# dev-board.net
KiCad netlist of a schematic drawn in EAGLE
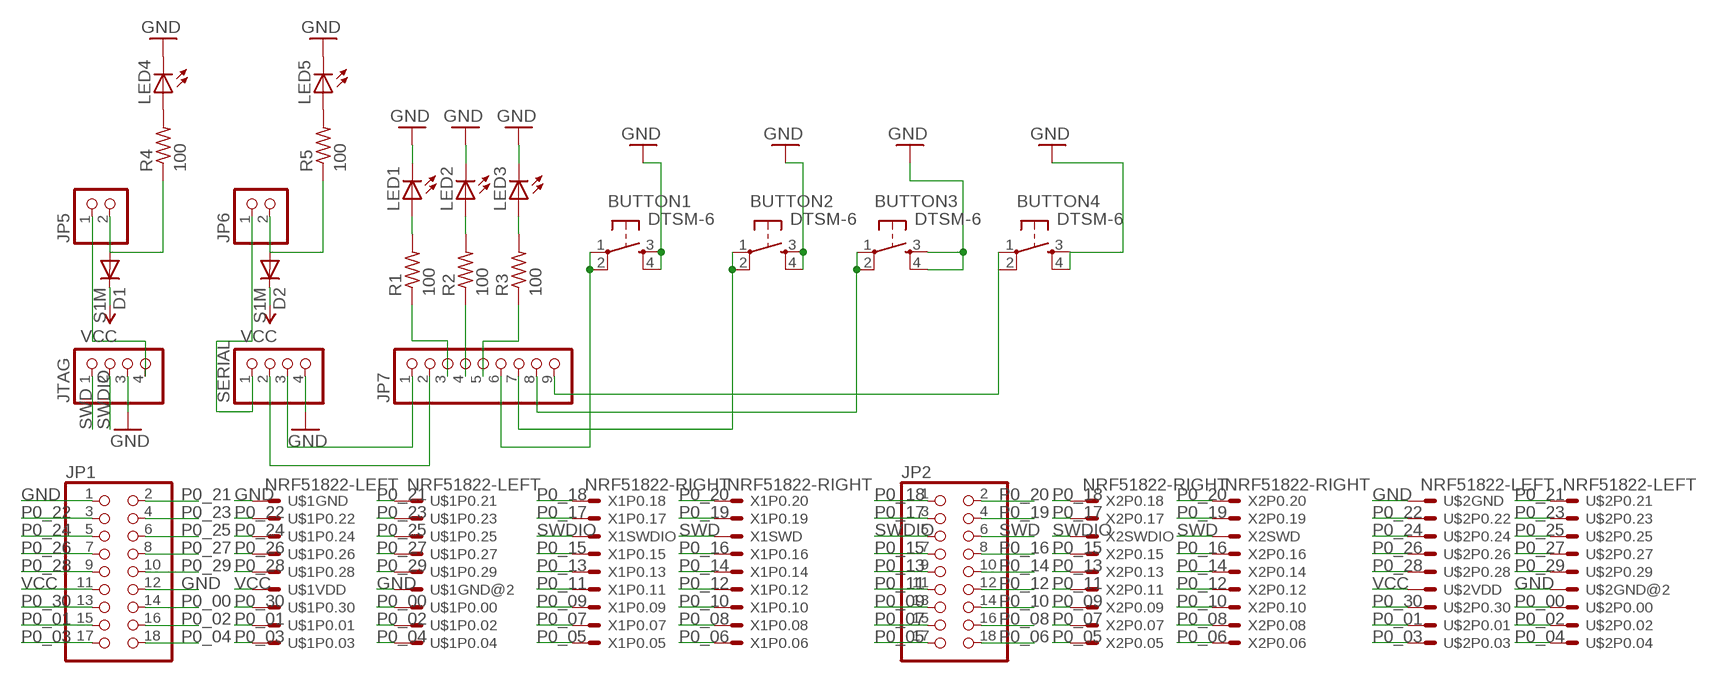
[diagram p0: schematic, sheet 1]

(export (version "E")
  (design (tool "Eeschema 10.0.6"))
  (components
    (comp (ref "BUTTON1")
      (value "DTSM-6")
      (footprint "eagle-import:DTSM-6")
      (libsource (lib "eagle-import") (part "DTSM-6"))
    )
    (comp (ref "BUTTON2")
      (value "DTSM-6")
      (footprint "eagle-import:DTSM-6")
      (libsource (lib "eagle-import") (part "DTSM-6"))
    )
    (comp (ref "BUTTON3")
      (value "DTSM-6")
      (footprint "eagle-import:DTSM-6")
      (libsource (lib "eagle-import") (part "DTSM-6"))
    )
    (comp (ref "BUTTON4")
      (value "DTSM-6")
      (footprint "eagle-import:DTSM-6")
      (libsource (lib "eagle-import") (part "DTSM-6"))
    )
    (comp (ref "D1")
      (value "S1M")
      (footprint "eagle-import:SMA")
      (libsource (lib "eagle-import") (part "S1M"))
    )
    (comp (ref "D2")
      (value "S1M")
      (footprint "eagle-import:SMA")
      (libsource (lib "eagle-import") (part "S1M"))
    )
    (comp (ref "JP1")
      (value "PINHD-2X9")
      (footprint "eagle-import:2X09")
      (libsource (lib "eagle-import") (part "PINHD-2X9"))
    )
    (comp (ref "JP2")
      (value "PINHD-2X9")
      (footprint "eagle-import:2X09")
      (libsource (lib "eagle-import") (part "PINHD-2X9"))
    )
    (comp (ref "JP5")
      (value "PINHD-1X2")
      (footprint "eagle-import:1X02")
      (libsource (lib "eagle-import") (part "PINHD-1X2"))
    )
    (comp (ref "JP6")
      (value "PINHD-1X2")
      (footprint "eagle-import:1X02")
      (libsource (lib "eagle-import") (part "PINHD-1X2"))
    )
    (comp (ref "JP7")
      (value "PINHD-1X9")
      (footprint "eagle-import:1X09")
      (libsource (lib "eagle-import") (part "PINHD-1X9"))
    )
    (comp (ref "JTAG")
      (value "PINHD-1X4")
      (footprint "eagle-import:1X04")
      (libsource (lib "eagle-import") (part "PINHD-1X4"))
    )
    (comp (ref "LED1")
      (value "LEDSML0603")
      (footprint "eagle-import:SML0603")
      (libsource (lib "eagle-import") (part "LEDSML0603"))
    )
    (comp (ref "LED2")
      (value "LEDSML0603")
      (footprint "eagle-import:SML0603")
      (libsource (lib "eagle-import") (part "LEDSML0603"))
    )
    (comp (ref "LED3")
      (value "LEDSML0603")
      (footprint "eagle-import:SML0603")
      (libsource (lib "eagle-import") (part "LEDSML0603"))
    )
    (comp (ref "LED4")
      (value "LEDSML0603")
      (footprint "eagle-import:SML0603")
      (libsource (lib "eagle-import") (part "LEDSML0603"))
    )
    (comp (ref "LED5")
      (value "LEDSML0603")
      (footprint "eagle-import:SML0603")
      (libsource (lib "eagle-import") (part "LEDSML0603"))
    )
    (comp (ref "R1")
      (value "100")
      (footprint "eagle-import:R0603")
      (libsource (lib "eagle-import") (part "R-US_R0603"))
    )
    (comp (ref "R2")
      (value "100")
      (footprint "eagle-import:R0603")
      (libsource (lib "eagle-import") (part "R-US_R0603"))
    )
    (comp (ref "R3")
      (value "100")
      (footprint "eagle-import:R0603")
      (libsource (lib "eagle-import") (part "R-US_R0603"))
    )
    (comp (ref "R4")
      (value "100")
      (footprint "eagle-import:R0603")
      (libsource (lib "eagle-import") (part "R-US_R0603"))
    )
    (comp (ref "R5")
      (value "100")
      (footprint "eagle-import:R0603")
      (libsource (lib "eagle-import") (part "R-US_R0603"))
    )
    (comp (ref "SERIAL")
      (value "PINHD-1X4")
      (footprint "eagle-import:1X04")
      (libsource (lib "eagle-import") (part "PINHD-1X4"))
    )
    (comp (ref "U$1")
      (value "NRF51822-LEFT")
      (footprint "eagle-import:NRF51822-LEFT")
      (fields (field (name "MPN") "NRF51822-left"))
      (libsource (lib "eagle-import") (part "NRF51822-LEFT"))
    )
    (comp (ref "U$2")
      (value "NRF51822-LEFT")
      (footprint "eagle-import:NRF51822-LEFT")
      (fields (field (name "MPN") "NRF51822-left"))
      (libsource (lib "eagle-import") (part "NRF51822-LEFT"))
    )
    (comp (ref "X1")
      (value "NRF51822-RIGHT")
      (footprint "eagle-import:NRF51822-RIGHT")
      (fields (field (name "MPN") "NRF51822-right"))
      (libsource (lib "eagle-import") (part "NRF51822-RIGHT"))
    )
    (comp (ref "X2")
      (value "NRF51822-RIGHT")
      (footprint "eagle-import:NRF51822-RIGHT")
      (fields (field (name "MPN") "NRF51822-right"))
      (libsource (lib "eagle-import") (part "NRF51822-RIGHT"))
    )
  )
  (nets
    (net (code "1") (name "/P0_00") (class "Default")
      (node (ref "JP1") (pin "14") (pinfunction "14_14") (pintype "passive"))
      (node (ref "U$1") (pin "14") (pinfunction "S_14") (pintype "passive"))
      (node (ref "U$2") (pin "14") (pinfunction "S_14") (pintype "passive"))
    )
    (net (code "2") (name "/P0_01") (class "Default")
      (node (ref "JP1") (pin "15") (pinfunction "15_15") (pintype "passive"))
      (node (ref "U$1") (pin "15") (pinfunction "S_15") (pintype "passive"))
      (node (ref "U$2") (pin "15") (pinfunction "S_15") (pintype "passive"))
    )
    (net (code "3") (name "/P0_02") (class "Default")
      (node (ref "JP1") (pin "16") (pinfunction "16_16") (pintype "passive"))
      (node (ref "U$1") (pin "16") (pinfunction "S_16") (pintype "passive"))
      (node (ref "U$2") (pin "16") (pinfunction "S_16") (pintype "passive"))
    )
    (net (code "4") (name "/P0_03") (class "Default")
      (node (ref "JP1") (pin "17") (pinfunction "17_17") (pintype "passive"))
      (node (ref "U$1") (pin "17") (pinfunction "S_17") (pintype "passive"))
      (node (ref "U$2") (pin "17") (pinfunction "S_17") (pintype "passive"))
    )
    (net (code "5") (name "/P0_04") (class "Default")
      (node (ref "JP1") (pin "18") (pinfunction "18_18") (pintype "passive"))
      (node (ref "U$1") (pin "18") (pinfunction "S_18") (pintype "passive"))
      (node (ref "U$2") (pin "18") (pinfunction "S_18") (pintype "passive"))
    )
    (net (code "6") (name "/P0_05") (class "Default")
      (node (ref "JP2") (pin "17") (pinfunction "17_17") (pintype "passive"))
      (node (ref "X1") (pin "17") (pinfunction "S_17") (pintype "passive"))
      (node (ref "X2") (pin "17") (pinfunction "S_17") (pintype "passive"))
    )
    (net (code "7") (name "/P0_06") (class "Default")
      (node (ref "JP2") (pin "18") (pinfunction "18_18") (pintype "passive"))
      (node (ref "X1") (pin "18") (pinfunction "S_18") (pintype "passive"))
      (node (ref "X2") (pin "18") (pinfunction "S_18") (pintype "passive"))
    )
    (net (code "8") (name "/P0_07") (class "Default")
      (node (ref "JP2") (pin "15") (pinfunction "15_15") (pintype "passive"))
      (node (ref "X1") (pin "15") (pinfunction "S_15") (pintype "passive"))
      (node (ref "X2") (pin "15") (pinfunction "S_15") (pintype "passive"))
    )
    (net (code "9") (name "/P0_08") (class "Default")
      (node (ref "JP2") (pin "16") (pinfunction "16_16") (pintype "passive"))
      (node (ref "X1") (pin "16") (pinfunction "S_16") (pintype "passive"))
      (node (ref "X2") (pin "16") (pinfunction "S_16") (pintype "passive"))
    )
    (net (code "10") (name "/P0_09") (class "Default")
      (node (ref "JP2") (pin "13") (pinfunction "13_13") (pintype "passive"))
      (node (ref "X1") (pin "13") (pinfunction "S_13") (pintype "passive"))
      (node (ref "X2") (pin "13") (pinfunction "S_13") (pintype "passive"))
    )
    (net (code "11") (name "/P0_10") (class "Default")
      (node (ref "JP2") (pin "14") (pinfunction "14_14") (pintype "passive"))
      (node (ref "X1") (pin "14") (pinfunction "S_14") (pintype "passive"))
      (node (ref "X2") (pin "14") (pinfunction "S_14") (pintype "passive"))
    )
    (net (code "12") (name "/P0_11") (class "Default")
      (node (ref "JP2") (pin "11") (pinfunction "11_11") (pintype "passive"))
      (node (ref "X1") (pin "11") (pinfunction "S_11") (pintype "passive"))
      (node (ref "X2") (pin "11") (pinfunction "S_11") (pintype "passive"))
    )
    (net (code "13") (name "/P0_12") (class "Default")
      (node (ref "JP2") (pin "12") (pinfunction "12_12") (pintype "passive"))
      (node (ref "X1") (pin "12") (pinfunction "S_12") (pintype "passive"))
      (node (ref "X2") (pin "12") (pinfunction "S_12") (pintype "passive"))
    )
    (net (code "14") (name "/P0_13") (class "Default")
      (node (ref "JP2") (pin "9") (pinfunction "9_9") (pintype "passive"))
      (node (ref "X1") (pin "9") (pinfunction "S_9") (pintype "passive"))
      (node (ref "X2") (pin "9") (pinfunction "S_9") (pintype "passive"))
    )
    (net (code "15") (name "/P0_14") (class "Default")
      (node (ref "JP2") (pin "10") (pinfunction "10_10") (pintype "passive"))
      (node (ref "X1") (pin "10") (pinfunction "S_10") (pintype "passive"))
      (node (ref "X2") (pin "10") (pinfunction "S_10") (pintype "passive"))
    )
    (net (code "16") (name "/P0_15") (class "Default")
      (node (ref "JP2") (pin "7") (pinfunction "7_7") (pintype "passive"))
      (node (ref "X1") (pin "7") (pinfunction "S_7") (pintype "passive"))
      (node (ref "X2") (pin "7") (pinfunction "S_7") (pintype "passive"))
    )
    (net (code "17") (name "/P0_16") (class "Default")
      (node (ref "JP2") (pin "8") (pinfunction "8_8") (pintype "passive"))
      (node (ref "X1") (pin "8") (pinfunction "S_8") (pintype "passive"))
      (node (ref "X2") (pin "8") (pinfunction "S_8") (pintype "passive"))
    )
    (net (code "18") (name "/P0_17") (class "Default")
      (node (ref "JP2") (pin "3") (pinfunction "3_3") (pintype "passive"))
      (node (ref "X1") (pin "3") (pinfunction "S_3") (pintype "passive"))
      (node (ref "X2") (pin "3") (pinfunction "S_3") (pintype "passive"))
    )
    (net (code "19") (name "/P0_18") (class "Default")
      (node (ref "JP2") (pin "1") (pinfunction "1_1") (pintype "passive"))
      (node (ref "X1") (pin "1") (pinfunction "S_1") (pintype "passive"))
      (node (ref "X2") (pin "1") (pinfunction "S_1") (pintype "passive"))
    )
    (net (code "20") (name "/P0_19") (class "Default")
      (node (ref "JP2") (pin "4") (pinfunction "4_4") (pintype "passive"))
      (node (ref "X1") (pin "4") (pinfunction "S_4") (pintype "passive"))
      (node (ref "X2") (pin "4") (pinfunction "S_4") (pintype "passive"))
    )
    (net (code "21") (name "/P0_20") (class "Default")
      (node (ref "JP2") (pin "2") (pinfunction "2_2") (pintype "passive"))
      (node (ref "X1") (pin "2") (pinfunction "S_2") (pintype "passive"))
      (node (ref "X2") (pin "2") (pinfunction "S_2") (pintype "passive"))
    )
    (net (code "22") (name "/P0_21") (class "Default")
      (node (ref "JP1") (pin "2") (pinfunction "2_2") (pintype "passive"))
      (node (ref "U$1") (pin "2") (pinfunction "S_2") (pintype "passive"))
      (node (ref "U$2") (pin "2") (pinfunction "S_2") (pintype "passive"))
    )
    (net (code "23") (name "/P0_22") (class "Default")
      (node (ref "JP1") (pin "3") (pinfunction "3_3") (pintype "passive"))
      (node (ref "U$1") (pin "3") (pinfunction "S_3") (pintype "passive"))
      (node (ref "U$2") (pin "3") (pinfunction "S_3") (pintype "passive"))
    )
    (net (code "24") (name "/P0_23") (class "Default")
      (node (ref "JP1") (pin "4") (pinfunction "4_4") (pintype "passive"))
      (node (ref "U$1") (pin "4") (pinfunction "S_4") (pintype "passive"))
      (node (ref "U$2") (pin "4") (pinfunction "S_4") (pintype "passive"))
    )
    (net (code "25") (name "/P0_24") (class "Default")
      (node (ref "JP1") (pin "5") (pinfunction "5_5") (pintype "passive"))
      (node (ref "U$1") (pin "5") (pinfunction "S_5") (pintype "passive"))
      (node (ref "U$2") (pin "5") (pinfunction "S_5") (pintype "passive"))
    )
    (net (code "26") (name "/P0_25") (class "Default")
      (node (ref "JP1") (pin "6") (pinfunction "6_6") (pintype "passive"))
      (node (ref "U$1") (pin "6") (pinfunction "S_6") (pintype "passive"))
      (node (ref "U$2") (pin "6") (pinfunction "S_6") (pintype "passive"))
    )
    (net (code "27") (name "/P0_26") (class "Default")
      (node (ref "JP1") (pin "7") (pinfunction "7_7") (pintype "passive"))
      (node (ref "U$1") (pin "7") (pinfunction "S_7") (pintype "passive"))
      (node (ref "U$2") (pin "7") (pinfunction "S_7") (pintype "passive"))
    )
    (net (code "28") (name "/P0_27") (class "Default")
      (node (ref "JP1") (pin "8") (pinfunction "8_8") (pintype "passive"))
      (node (ref "U$1") (pin "8") (pinfunction "S_8") (pintype "passive"))
      (node (ref "U$2") (pin "8") (pinfunction "S_8") (pintype "passive"))
    )
    (net (code "29") (name "/P0_28") (class "Default")
      (node (ref "JP1") (pin "9") (pinfunction "9_9") (pintype "passive"))
      (node (ref "U$1") (pin "9") (pinfunction "S_9") (pintype "passive"))
      (node (ref "U$2") (pin "9") (pinfunction "S_9") (pintype "passive"))
    )
    (net (code "30") (name "/P0_29") (class "Default")
      (node (ref "JP1") (pin "10") (pinfunction "10_10") (pintype "passive"))
      (node (ref "U$1") (pin "10") (pinfunction "S_10") (pintype "passive"))
      (node (ref "U$2") (pin "10") (pinfunction "S_10") (pintype "passive"))
    )
    (net (code "31") (name "/P0_30") (class "Default")
      (node (ref "JP1") (pin "13") (pinfunction "13_13") (pintype "passive"))
      (node (ref "U$1") (pin "13") (pinfunction "S_13") (pintype "passive"))
      (node (ref "U$2") (pin "13") (pinfunction "S_13") (pintype "passive"))
    )
    (net (code "32") (name "/SWD") (class "Default")
      (node (ref "JP2") (pin "6") (pinfunction "6_6") (pintype "passive"))
      (node (ref "JTAG") (pin "1") (pinfunction "1_1") (pintype "passive"))
      (node (ref "X1") (pin "6") (pinfunction "S_6") (pintype "passive"))
      (node (ref "X2") (pin "6") (pinfunction "S_6") (pintype "passive"))
    )
    (net (code "33") (name "/SWDIO") (class "Default")
      (node (ref "JP2") (pin "5") (pinfunction "5_5") (pintype "passive"))
      (node (ref "JTAG") (pin "2") (pinfunction "2_2") (pintype "passive"))
      (node (ref "X1") (pin "5") (pinfunction "S_5") (pintype "passive"))
      (node (ref "X2") (pin "5") (pinfunction "S_5") (pintype "passive"))
    )
    (net (code "34") (name "GND") (class "Default")
      (node (ref "BUTTON1") (pin "3") (pinfunction "3_3") (pintype "passive"))
      (node (ref "BUTTON1") (pin "4") (pinfunction "4_4") (pintype "passive"))
      (node (ref "BUTTON2") (pin "3") (pinfunction "3_3") (pintype "passive"))
      (node (ref "BUTTON2") (pin "4") (pinfunction "4_4") (pintype "passive"))
      (node (ref "BUTTON3") (pin "3") (pinfunction "3_3") (pintype "passive"))
      (node (ref "BUTTON3") (pin "4") (pinfunction "4_4") (pintype "passive"))
      (node (ref "BUTTON4") (pin "3") (pinfunction "3_3") (pintype "passive"))
      (node (ref "BUTTON4") (pin "4") (pinfunction "4_4") (pintype "passive"))
      (node (ref "JP1") (pin "1") (pinfunction "1_1") (pintype "passive"))
      (node (ref "JP1") (pin "12") (pinfunction "12_12") (pintype "passive"))
      (node (ref "JTAG") (pin "3") (pinfunction "3_3") (pintype "passive"))
      (node (ref "LED1") (pin "C") (pinfunction "C_C") (pintype "passive"))
      (node (ref "LED2") (pin "C") (pinfunction "C_C") (pintype "passive"))
      (node (ref "LED3") (pin "C") (pinfunction "C_C") (pintype "passive"))
      (node (ref "LED4") (pin "C") (pinfunction "C_C") (pintype "passive"))
      (node (ref "LED5") (pin "C") (pinfunction "C_C") (pintype "passive"))
      (node (ref "SERIAL") (pin "4") (pinfunction "4_4") (pintype "passive"))
      (node (ref "U$1") (pin "1") (pinfunction "S_1") (pintype "passive"))
      (node (ref "U$1") (pin "12") (pinfunction "S_12") (pintype "passive"))
      (node (ref "U$2") (pin "1") (pinfunction "S_1") (pintype "passive"))
      (node (ref "U$2") (pin "12") (pinfunction "S_12") (pintype "passive"))
    )
    (net (code "35") (name "Net-(BUTTON1-Pad1)") (class "Default")
      (node (ref "BUTTON1") (pin "1") (pinfunction "1_1") (pintype "passive"))
      (node (ref "BUTTON1") (pin "2") (pinfunction "2_2") (pintype "passive"))
      (node (ref "JP7") (pin "6") (pinfunction "6_6") (pintype "passive"))
    )
    (net (code "36") (name "Net-(BUTTON2-Pad1)") (class "Default")
      (node (ref "BUTTON2") (pin "1") (pinfunction "1_1") (pintype "passive"))
      (node (ref "BUTTON2") (pin "2") (pinfunction "2_2") (pintype "passive"))
      (node (ref "JP7") (pin "7") (pinfunction "7_7") (pintype "passive"))
    )
    (net (code "37") (name "Net-(BUTTON3-Pad1)") (class "Default")
      (node (ref "BUTTON3") (pin "1") (pinfunction "1_1") (pintype "passive"))
      (node (ref "BUTTON3") (pin "2") (pinfunction "2_2") (pintype "passive"))
      (node (ref "JP7") (pin "8") (pinfunction "8_8") (pintype "passive"))
    )
    (net (code "38") (name "Net-(BUTTON4-Pad1)") (class "Default")
      (node (ref "BUTTON4") (pin "1") (pinfunction "1_1") (pintype "passive"))
      (node (ref "BUTTON4") (pin "2") (pinfunction "2_2") (pintype "passive"))
      (node (ref "JP7") (pin "9") (pinfunction "9_9") (pintype "passive"))
    )
    (net (code "39") (name "Net-(D1-PadA)") (class "Default")
      (node (ref "D1") (pin "A") (pinfunction "A_A") (pintype "passive"))
      (node (ref "JP5") (pin "2") (pinfunction "2_2") (pintype "passive"))
      (node (ref "R4") (pin "1") (pinfunction "1_1") (pintype "passive"))
    )
    (net (code "40") (name "Net-(D2-PadA)") (class "Default")
      (node (ref "D2") (pin "A") (pinfunction "A_A") (pintype "passive"))
      (node (ref "JP6") (pin "2") (pinfunction "2_2") (pintype "passive"))
      (node (ref "R5") (pin "1") (pinfunction "1_1") (pintype "passive"))
    )
    (net (code "41") (name "Net-(JP5-Pad1)") (class "Default")
      (node (ref "JP5") (pin "1") (pinfunction "1_1") (pintype "passive"))
      (node (ref "JTAG") (pin "4") (pinfunction "4_4") (pintype "passive"))
    )
    (net (code "42") (name "Net-(JP6-Pad1)") (class "Default")
      (node (ref "JP6") (pin "1") (pinfunction "1_1") (pintype "passive"))
      (node (ref "SERIAL") (pin "1") (pinfunction "1_1") (pintype "passive"))
    )
    (net (code "43") (name "Net-(JP7-Pad1)") (class "Default")
      (node (ref "JP7") (pin "1") (pinfunction "1_1") (pintype "passive"))
      (node (ref "SERIAL") (pin "3") (pinfunction "3_3") (pintype "passive"))
    )
    (net (code "44") (name "Net-(JP7-Pad2)") (class "Default")
      (node (ref "JP7") (pin "2") (pinfunction "2_2") (pintype "passive"))
      (node (ref "SERIAL") (pin "2") (pinfunction "2_2") (pintype "passive"))
    )
    (net (code "45") (name "Net-(JP7-Pad3)") (class "Default")
      (node (ref "JP7") (pin "3") (pinfunction "3_3") (pintype "passive"))
      (node (ref "R1") (pin "1") (pinfunction "1_1") (pintype "passive"))
    )
    (net (code "46") (name "Net-(JP7-Pad4)") (class "Default")
      (node (ref "JP7") (pin "4") (pinfunction "4_4") (pintype "passive"))
      (node (ref "R2") (pin "1") (pinfunction "1_1") (pintype "passive"))
    )
    (net (code "47") (name "Net-(JP7-Pad5)") (class "Default")
      (node (ref "JP7") (pin "5") (pinfunction "5_5") (pintype "passive"))
      (node (ref "R3") (pin "1") (pinfunction "1_1") (pintype "passive"))
    )
    (net (code "48") (name "Net-(LED1-PadA)") (class "Default")
      (node (ref "LED1") (pin "A") (pinfunction "A_A") (pintype "passive"))
      (node (ref "R1") (pin "2") (pinfunction "2_2") (pintype "passive"))
    )
    (net (code "49") (name "Net-(LED2-PadA)") (class "Default")
      (node (ref "LED2") (pin "A") (pinfunction "A_A") (pintype "passive"))
      (node (ref "R2") (pin "2") (pinfunction "2_2") (pintype "passive"))
    )
    (net (code "50") (name "Net-(LED3-PadA)") (class "Default")
      (node (ref "LED3") (pin "A") (pinfunction "A_A") (pintype "passive"))
      (node (ref "R3") (pin "2") (pinfunction "2_2") (pintype "passive"))
    )
    (net (code "51") (name "Net-(LED4-PadA)") (class "Default")
      (node (ref "LED4") (pin "A") (pinfunction "A_A") (pintype "passive"))
      (node (ref "R4") (pin "2") (pinfunction "2_2") (pintype "passive"))
    )
    (net (code "52") (name "Net-(LED5-PadA)") (class "Default")
      (node (ref "LED5") (pin "A") (pinfunction "A_A") (pintype "passive"))
      (node (ref "R5") (pin "2") (pinfunction "2_2") (pintype "passive"))
    )
    (net (code "53") (name "VCC") (class "Default")
      (node (ref "D1") (pin "C") (pinfunction "C_C") (pintype "passive"))
      (node (ref "D2") (pin "C") (pinfunction "C_C") (pintype "passive"))
      (node (ref "JP1") (pin "11") (pinfunction "11_11") (pintype "passive"))
      (node (ref "U$1") (pin "11") (pinfunction "S_11") (pintype "passive"))
      (node (ref "U$2") (pin "11") (pinfunction "S_11") (pintype "passive"))
    )
  )
)
